# STM32F1_microcontroller.net
KiCad netlist of a schematic drawn in Altium Designer
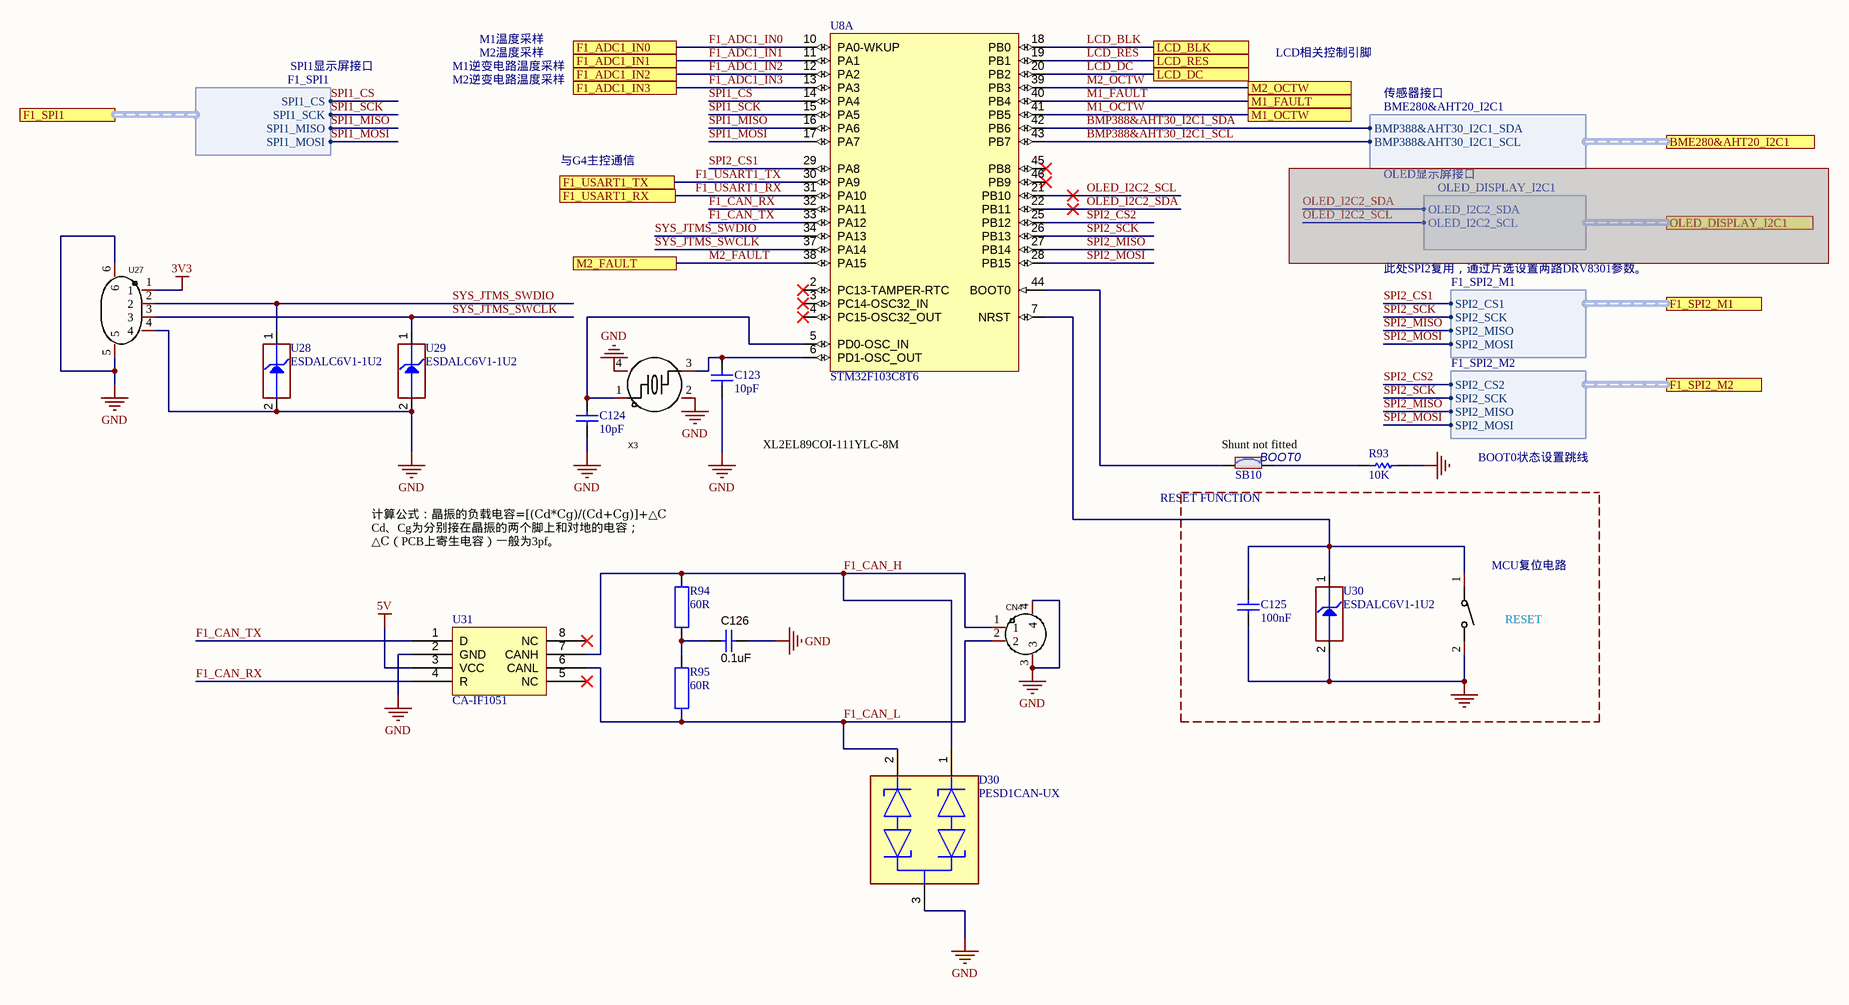
[diagram p0: STM32F1_microcontroller.SchDoc]

(export (version "E")
  (design (tool "Eeschema 10.0.6"))
  (components
    (comp (ref "C123")
      (value "10pF")
      (footprint "C0402")
      (description "Capacitor, MLCC, 5.1pF, 50V, NPO, +-0.25pF, 0402, T=0.5mm")
      (fields
        (field (name "INTERNAL_PART_NUMBER") "MCD-00003")
        (field (name "MANUFACTURER_PART_NUMBER") "CC0402CRNPO9BN5R1")
        (field (name "PROVIDED_BY") "SUBCO")
      )
      (libsource (lib "MCD_PARTS_database") (part "Capacitor"))
    )
    (comp (ref "C124")
      (value "10pF")
      (footprint "C0402")
      (description "Capacitor, MLCC, 5.1pF, 50V, NPO, +-0.25pF, 0402, T=0.5mm")
      (fields
        (field (name "INTERNAL_PART_NUMBER") "MCD-00003")
        (field (name "MANUFACTURER_PART_NUMBER") "CC0402CRNPO9BN5R1")
        (field (name "PROVIDED_BY") "SUBCO")
      )
      (libsource (lib "MCD_PARTS_database") (part "Capacitor"))
    )
    (comp (ref "C125")
      (value "100nF")
      (footprint "C0402")
      (description "Capacitor, MLCC, 100nF, 16V, X7R, 10%, 0402, T=0,5mm")
      (fields
        (field (name "INTERNAL_PART_NUMBER") "MCD-00102")
        (field (name "MANUFACTURER_PART_NUMBER") "CC0402KRX7R7BB104")
        (field (name "PROVIDED_BY") "Subcon")
      )
      (libsource (lib "MCD_PARTS_database") (part "Capacitor"))
    )
    (comp (ref "C126")
      (value "GRM188R61E105KA12D")
      (footprint "0603L")
      (description "CAP, CERM, 0.1uF, 25V, +/-10%, X5R, 0603")
      (fields
        (field (name "VALUEDISPLAYED") "0.1uF")
        (field (name "MANUFACTURER") "MuRata")
        (field (name "PUBLISHER") "Texas Instruments")
      )
      (libsource (lib "Capacitor_Ceramic") (part "GRM188R61E105KA12D"))
    )
    (comp (ref "CN4")
      (value "WAFER-GH1.25-2PWB")
      (footprint "CONN-TH_2P-P1.25_XUNPU_WAFER-GH1.25-2PWB")
      (fields (field (name "MANUFACTURER") "XUNPU(讯普)"))
      (libsource (lib "two_ax_PCB") (part "WAFER-GH1.25-2PWB"))
    )
    (comp (ref "D30")
      (value "PESD1CAN-UX")
      (footprint "FP-SOT323-MFG")
      (description "TVS DIODE 24V 50V SC70-3")
      (libsource (lib "Altium Content Vault") (part "04d57993b6b7b0f5b3c95ba4f97dea0"))
    )
    (comp (ref "R93")
      (value "10K")
      (footprint "R0603")
      (description "Resistor,10K,0603,1%,1/10W")
      (fields
        (field (name "INTERNAL_PART_NUMBER") "MCD-00220")
        (field (name "MANUFACTURER_PART_NUMBER") "RC0603FR-0710KL")
        (field (name "PROVIDED_BY") "Subcon")
      )
      (libsource (lib "MCD_PARTS_database") (part "Resistor"))
    )
    (comp (ref "R94")
      (value "60R")
      (footprint "RESC1608X55N")
      (description "RES SMD 60 OHM 1% 1/10W 0603")
      (fields
        (field (name "MANUFACTURER") "Yageo")
        (field (name "MANUFACTURER PART NUMBER") "RC0603FR-07120RL")
      )
      (libsource (lib "CustomComponents") (part "RC0603FR-07120RL"))
    )
    (comp (ref "R95")
      (value "60R")
      (footprint "RESC1608X55N")
      (description "RES SMD 60 OHM 1% 1/10W 0603")
      (fields
        (field (name "MANUFACTURER") "Yageo")
        (field (name "MANUFACTURER PART NUMBER") "RC0603FR-07120RL")
      )
      (libsource (lib "CustomComponents") (part "RC0603FR-07120RL"))
    )
    (comp (ref "SB10")
      (value "MCD-00071")
      (footprint "SOLDER-BRIDGE_R0603-0R")
      (description "Solder Bridge ON")
      (fields
        (field (name "MANUFACTURER_PART_NUMBER") "RC0603JR-070RL")
        (field (name "MANUFACTURER") "YAGEO")
        (field (name "PROVIDED_BY") "SUBCO")
      )
      (libsource (lib "mb1367") (part "MCD-00071"))
    )
    (comp (ref "SW2")
      (value "TS-1088-AR02016")
      (footprint "SW-SMD_L3.9-W3.0-P4.45")
      (fields (field (name "MANUFACTURER") "XUNPU(讯普)"))
      (libsource (lib "mb1367") (part "TS-1088-AR02016"))
    )
    (comp (ref "U8")
      (value "STM32F103C8T6")
      (footprint "STM-LQFP48_L")
      (libsource (lib "Altium Content Vault") (part "MC-ARM-STM32F103X8_B-SQ48"))
    )
    (comp (ref "U27")
      (value "WAFER-GH1.25-4PWB")
      (footprint "CONN-SMD_4P-P1.25_XUNPU_WAFER-GH1.25-4PWB")
      (fields (field (name "MANUFACTURER") "XUNPU(讯普)"))
      (libsource (lib "two_ax_PCB") (part "WAFER-GH1.25-4PWB"))
    )
    (comp (ref "U28")
      (value "ESDALC6V1-1U2")
      (footprint "ESD_ST0201")
      (description "ESD protection 6V1")
      (fields
        (field (name "INTERNAL_PART_NUMBER") "MCD-00170")
        (field (name "MANUFACTURER") "STMICROELECTRONICS")
        (field (name "PROVIDED_BY") "Subcon")
      )
      (libsource (lib "MCD_PARTS_database") (part "ESD-TRANSIL"))
    )
    (comp (ref "U29")
      (value "ESDALC6V1-1U2")
      (footprint "ESD_ST0201")
      (description "ESD protection 6V1")
      (fields
        (field (name "INTERNAL_PART_NUMBER") "MCD-00170")
        (field (name "MANUFACTURER") "STMICROELECTRONICS")
        (field (name "PROVIDED_BY") "Subcon")
      )
      (libsource (lib "MCD_PARTS_database") (part "ESD-TRANSIL"))
    )
    (comp (ref "U30")
      (value "ESDALC6V1-1U2")
      (footprint "ESD_ST0201")
      (description "ESD protection 6V1")
      (fields
        (field (name "INTERNAL_PART_NUMBER") "MCD-00170")
        (field (name "MANUFACTURER") "STMICROELECTRONICS")
        (field (name "PROVIDED_BY") "Subcon")
      )
      (libsource (lib "MCD_PARTS_database") (part "ESD-TRANSIL"))
    )
    (comp (ref "U31")
      (value "CA-IF1051")
      (footprint "SOIC127P600X175-8N")
      (fields
        (field (name "MANUFACTURER") "Texas Instruments")
        (field (name "MANUFACTURER PART NUMBER") "CA-IF1051")
      )
      (libsource (lib "CustomComponents") (part "SN65HVD232D"))
    )
    (comp (ref "X3")
      (value "8MHz")
      (footprint "CRYSTAL-SMD_4P-L3.2-W2.5-BL-1")
      (fields
        (field (name "MANUFACTURER") "YXC(扬兴晶振)")
        (field (name "MANUFACTURER PART") "XL2EL89COI-111YLC-8M")
      )
      (libsource (lib "two_ax_PCB") (part "XL2EL89COI-111YLC-8M"))
    )
  )
  (nets
    (net (code "6") (name "/BMP388&AHT30_I2C1_SCL") (class "Default")
      (node (ref "U8") (pin "43") (pinfunction "PB7_43") (pintype "bidirectional"))
    )
    (net (code "7") (name "/BMP388&AHT30_I2C1_SDA") (class "Default")
      (node (ref "U8") (pin "42") (pinfunction "PB6_42") (pintype "bidirectional"))
    )
    (net (code "8") (name "/F1_ADC1_IN0") (class "Default")
      (node (ref "U8") (pin "10") (pinfunction "PA0-WKUP_10") (pintype "bidirectional"))
    )
    (net (code "9") (name "/F1_ADC1_IN1") (class "Default")
      (node (ref "U8") (pin "11") (pinfunction "PA1_11") (pintype "bidirectional"))
    )
    (net (code "10") (name "/F1_ADC1_IN2") (class "Default")
      (node (ref "U8") (pin "12") (pinfunction "PA2_12") (pintype "bidirectional"))
    )
    (net (code "11") (name "/F1_ADC1_IN3") (class "Default")
      (node (ref "U8") (pin "13") (pinfunction "PA3_13") (pintype "bidirectional"))
    )
    (net (code "12") (name "/F1_CAN_H") (class "Default")
      (node (ref "CN4") (pin "1") (pinfunction "1_1") (pintype "passive"))
      (node (ref "D30") (pin "1") (pinfunction "cathode_1_1") (pintype "passive"))
      (node (ref "R94") (pin "2") (pinfunction "0_2") (pintype "passive"))
      (node (ref "U31") (pin "7") (pinfunction "CANH_7") (pintype "passive"))
    )
    (net (code "13") (name "/F1_CAN_L") (class "Default")
      (node (ref "CN4") (pin "2") (pinfunction "2_2") (pintype "passive"))
      (node (ref "D30") (pin "2") (pinfunction "cathode_2_2") (pintype "passive"))
      (node (ref "R95") (pin "1") (pinfunction "0_1") (pintype "passive"))
      (node (ref "U31") (pin "6") (pinfunction "CANL_6") (pintype "passive"))
    )
    (net (code "14") (name "/F1_CAN_RX") (class "Default")
      (node (ref "U31") (pin "4") (pinfunction "R_4") (pintype "passive"))
      (node (ref "U8") (pin "32") (pinfunction "PA11_32") (pintype "bidirectional"))
    )
    (net (code "15") (name "/F1_CAN_TX") (class "Default")
      (node (ref "U31") (pin "1") (pinfunction "D_1") (pintype "passive"))
      (node (ref "U8") (pin "33") (pinfunction "PA12_33") (pintype "bidirectional"))
    )
    (net (code "16") (name "/F1_USART1_RX") (class "Default")
      (node (ref "U8") (pin "31") (pinfunction "PA10_31") (pintype "bidirectional"))
    )
    (net (code "17") (name "/F1_USART1_TX") (class "Default")
      (node (ref "U8") (pin "30") (pinfunction "PA9_30") (pintype "bidirectional"))
    )
    (net (code "18") (name "/LCD_BLK") (class "Default")
      (node (ref "U8") (pin "18") (pinfunction "PB0_18") (pintype "bidirectional"))
    )
    (net (code "19") (name "/LCD_DC") (class "Default")
      (node (ref "U8") (pin "20") (pinfunction "PB2_20") (pintype "bidirectional"))
    )
    (net (code "20") (name "/LCD_RES") (class "Default")
      (node (ref "U8") (pin "19") (pinfunction "PB1_19") (pintype "bidirectional"))
    )
    (net (code "21") (name "/M1_FAULT") (class "Default")
      (node (ref "U8") (pin "40") (pinfunction "PB4_40") (pintype "bidirectional"))
    )
    (net (code "22") (name "/M1_OCTW") (class "Default")
      (node (ref "U8") (pin "41") (pinfunction "PB5_41") (pintype "bidirectional"))
    )
    (net (code "23") (name "/M2_FAULT") (class "Default")
      (node (ref "U8") (pin "38") (pinfunction "PA15_38") (pintype "bidirectional"))
    )
    (net (code "24") (name "/M2_OCTW") (class "Default")
      (node (ref "U8") (pin "39") (pinfunction "PB3_39") (pintype "bidirectional"))
    )
    (net (code "25") (name "/OLED_I2C2_SCL") (class "Default")
      (node (ref "U8") (pin "21") (pinfunction "PB10_21") (pintype "bidirectional"))
    )
    (net (code "26") (name "/OLED_I2C2_SDA") (class "Default")
      (node (ref "U8") (pin "22") (pinfunction "PB11_22") (pintype "bidirectional"))
    )
    (net (code "27") (name "/SPI1_CS") (class "Default")
      (node (ref "U8") (pin "14") (pinfunction "PA4_14") (pintype "bidirectional"))
    )
    (net (code "28") (name "/SPI1_MISO") (class "Default")
      (node (ref "U8") (pin "16") (pinfunction "PA6_16") (pintype "bidirectional"))
    )
    (net (code "29") (name "/SPI1_MOSI") (class "Default")
      (node (ref "U8") (pin "17") (pinfunction "PA7_17") (pintype "bidirectional"))
    )
    (net (code "30") (name "/SPI1_SCK") (class "Default")
      (node (ref "U8") (pin "15") (pinfunction "PA5_15") (pintype "bidirectional"))
    )
    (net (code "31") (name "/SPI2_CS1") (class "Default")
      (node (ref "U8") (pin "29") (pinfunction "PA8_29") (pintype "bidirectional"))
    )
    (net (code "32") (name "/SPI2_CS2") (class "Default")
      (node (ref "U8") (pin "25") (pinfunction "PB12_25") (pintype "bidirectional"))
    )
    (net (code "33") (name "/SPI2_MISO") (class "Default")
      (node (ref "U8") (pin "27") (pinfunction "PB14_27") (pintype "bidirectional"))
    )
    (net (code "34") (name "/SPI2_MOSI") (class "Default")
      (node (ref "U8") (pin "28") (pinfunction "PB15_28") (pintype "bidirectional"))
    )
    (net (code "35") (name "/SPI2_SCK") (class "Default")
      (node (ref "U8") (pin "26") (pinfunction "PB13_26") (pintype "bidirectional"))
    )
    (net (code "36") (name "/SYS_JTMS_SWCLK") (class "Default")
      (node (ref "U27") (pin "3") (pinfunction "3_3") (pintype "passive"))
      (node (ref "U29") (pin "1") (pinfunction "IO1_1") (pintype "passive"))
      (node (ref "U8") (pin "37") (pinfunction "PA14_37") (pintype "bidirectional"))
    )
    (net (code "37") (name "/SYS_JTMS_SWDIO") (class "Default")
      (node (ref "U27") (pin "2") (pinfunction "2_2") (pintype "passive"))
      (node (ref "U28") (pin "1") (pinfunction "IO1_1") (pintype "passive"))
      (node (ref "U8") (pin "34") (pinfunction "PA13_34") (pintype "bidirectional"))
    )
    (net (code "43") (name "3V3") (class "Default")
      (node (ref "U27") (pin "1") (pinfunction "1_1") (pintype "passive"))
    )
    (net (code "44") (name "5V") (class "Default")
      (node (ref "U31") (pin "3") (pinfunction "VCC_3") (pintype "passive"))
    )
    (net (code "45") (name "GND") (class "Default")
      (node (ref "C123") (pin "2") (pinfunction "2_2") (pintype "passive"))
      (node (ref "C124") (pin "2") (pinfunction "2_2") (pintype "passive"))
      (node (ref "C125") (pin "1") (pinfunction "1_1") (pintype "passive"))
      (node (ref "C126") (pin "2") (pinfunction "2_2") (pintype "passive"))
      (node (ref "CN4") (pin "3") (pinfunction "3_3") (pintype "passive"))
      (node (ref "CN4") (pin "4") (pinfunction "4_4") (pintype "passive"))
      (node (ref "D30") (pin "3") (pinfunction "common_cathode_3") (pintype "passive"))
      (node (ref "R93") (pin "1") (pinfunction "1_1") (pintype "passive"))
      (node (ref "SW2") (pin "2") (pinfunction "2_2") (pintype "passive"))
      (node (ref "U27") (pin "4") (pinfunction "4_4") (pintype "passive"))
      (node (ref "U27") (pin "5") (pinfunction "5_5") (pintype "passive"))
      (node (ref "U27") (pin "6") (pinfunction "6_6") (pintype "passive"))
      (node (ref "U28") (pin "2") (pinfunction "GND_2") (pintype "passive"))
      (node (ref "U29") (pin "2") (pinfunction "GND_2") (pintype "passive"))
      (node (ref "U30") (pin "2") (pinfunction "GND_2") (pintype "passive"))
      (node (ref "U31") (pin "2") (pinfunction "GND_2") (pintype "passive"))
      (node (ref "X3") (pin "2") (pinfunction "GND_2") (pintype "passive"))
      (node (ref "X3") (pin "4") (pinfunction "GND_4") (pintype "passive"))
    )
    (net (code "46") (name "Net-(C126-Pad1)") (class "Default")
      (node (ref "C126") (pin "1") (pinfunction "1_1") (pintype "passive"))
      (node (ref "R94") (pin "1") (pinfunction "0_1") (pintype "passive"))
      (node (ref "R95") (pin "2") (pinfunction "0_2") (pintype "passive"))
    )
    (net (code "47") (name "Net-(R93-Pad2)") (class "Default")
      (node (ref "R93") (pin "2") (pinfunction "2_2") (pintype "passive"))
      (node (ref "SB10") (pin "2") (pinfunction "2_2") (pintype "passive"))
    )
    (net (code "48") (name "Net-(U8A-BOOT0)") (class "Default")
      (node (ref "SB10") (pin "1") (pinfunction "1_1") (pintype "passive"))
      (node (ref "U8") (pin "44") (pinfunction "BOOT0_44") (pintype "input"))
    )
    (net (code "49") (name "Net-(U8A-PD0-OSC_IN)") (class "Default")
      (node (ref "C124") (pin "1") (pinfunction "1_1") (pintype "passive"))
      (node (ref "U8") (pin "5") (pinfunction "PD0-OSC_IN_5") (pintype "bidirectional"))
      (node (ref "X3") (pin "1") (pinfunction "1_1") (pintype "passive"))
    )
    (net (code "50") (name "Net-(U8A-PD1-OSC_OUT)") (class "Default")
      (node (ref "C123") (pin "1") (pinfunction "1_1") (pintype "passive"))
      (node (ref "U8") (pin "6") (pinfunction "PD1-OSC_OUT_6") (pintype "bidirectional"))
      (node (ref "X3") (pin "3") (pinfunction "3_3") (pintype "passive"))
    )
    (net (code "51") (name "Net-(U30-IO1)") (class "Default")
      (node (ref "C125") (pin "2") (pinfunction "2_2") (pintype "passive"))
      (node (ref "SW2") (pin "1") (pinfunction "1_1") (pintype "passive"))
      (node (ref "U30") (pin "1") (pinfunction "IO1_1") (pintype "passive"))
      (node (ref "U8") (pin "7") (pinfunction "NRST_7") (pintype "bidirectional"))
    )
    (net (code "52") (name "unconnected-(U8A-PB8-Pad45)") (class "Default")
      (node (ref "U8") (pin "45") (pinfunction "PB8_45") (pintype "bidirectional+no_connect"))
    )
    (net (code "53") (name "unconnected-(U8A-PB9-Pad46)") (class "Default")
      (node (ref "U8") (pin "46") (pinfunction "PB9_46") (pintype "bidirectional+no_connect"))
    )
    (net (code "54") (name "unconnected-(U8A-PC13-TAMPER-RTC-Pad2)") (class "Default")
      (node (ref "U8") (pin "2") (pinfunction "PC13-TAMPER-RTC_2") (pintype "bidirectional+no_connect"))
    )
    (net (code "55") (name "unconnected-(U8A-PC14-OSC32_IN-Pad3)") (class "Default")
      (node (ref "U8") (pin "3") (pinfunction "PC14-OSC32_IN_3") (pintype "bidirectional+no_connect"))
    )
    (net (code "56") (name "unconnected-(U8A-PC15-OSC32_OUT-Pad4)") (class "Default")
      (node (ref "U8") (pin "4") (pinfunction "PC15-OSC32_OUT_4") (pintype "bidirectional+no_connect"))
    )
    (net (code "57") (name "unconnected-(U31-NC-Pad5)") (class "Default")
      (node (ref "U31") (pin "5") (pinfunction "NC_5") (pintype "passive+no_connect"))
    )
    (net (code "58") (name "unconnected-(U31-NC-Pad8)") (class "Default")
      (node (ref "U31") (pin "8") (pinfunction "NC_8") (pintype "passive+no_connect"))
    )
  )
)
